# bluz_cr2477_v1.net
KiCad netlist of a schematic drawn in EAGLE
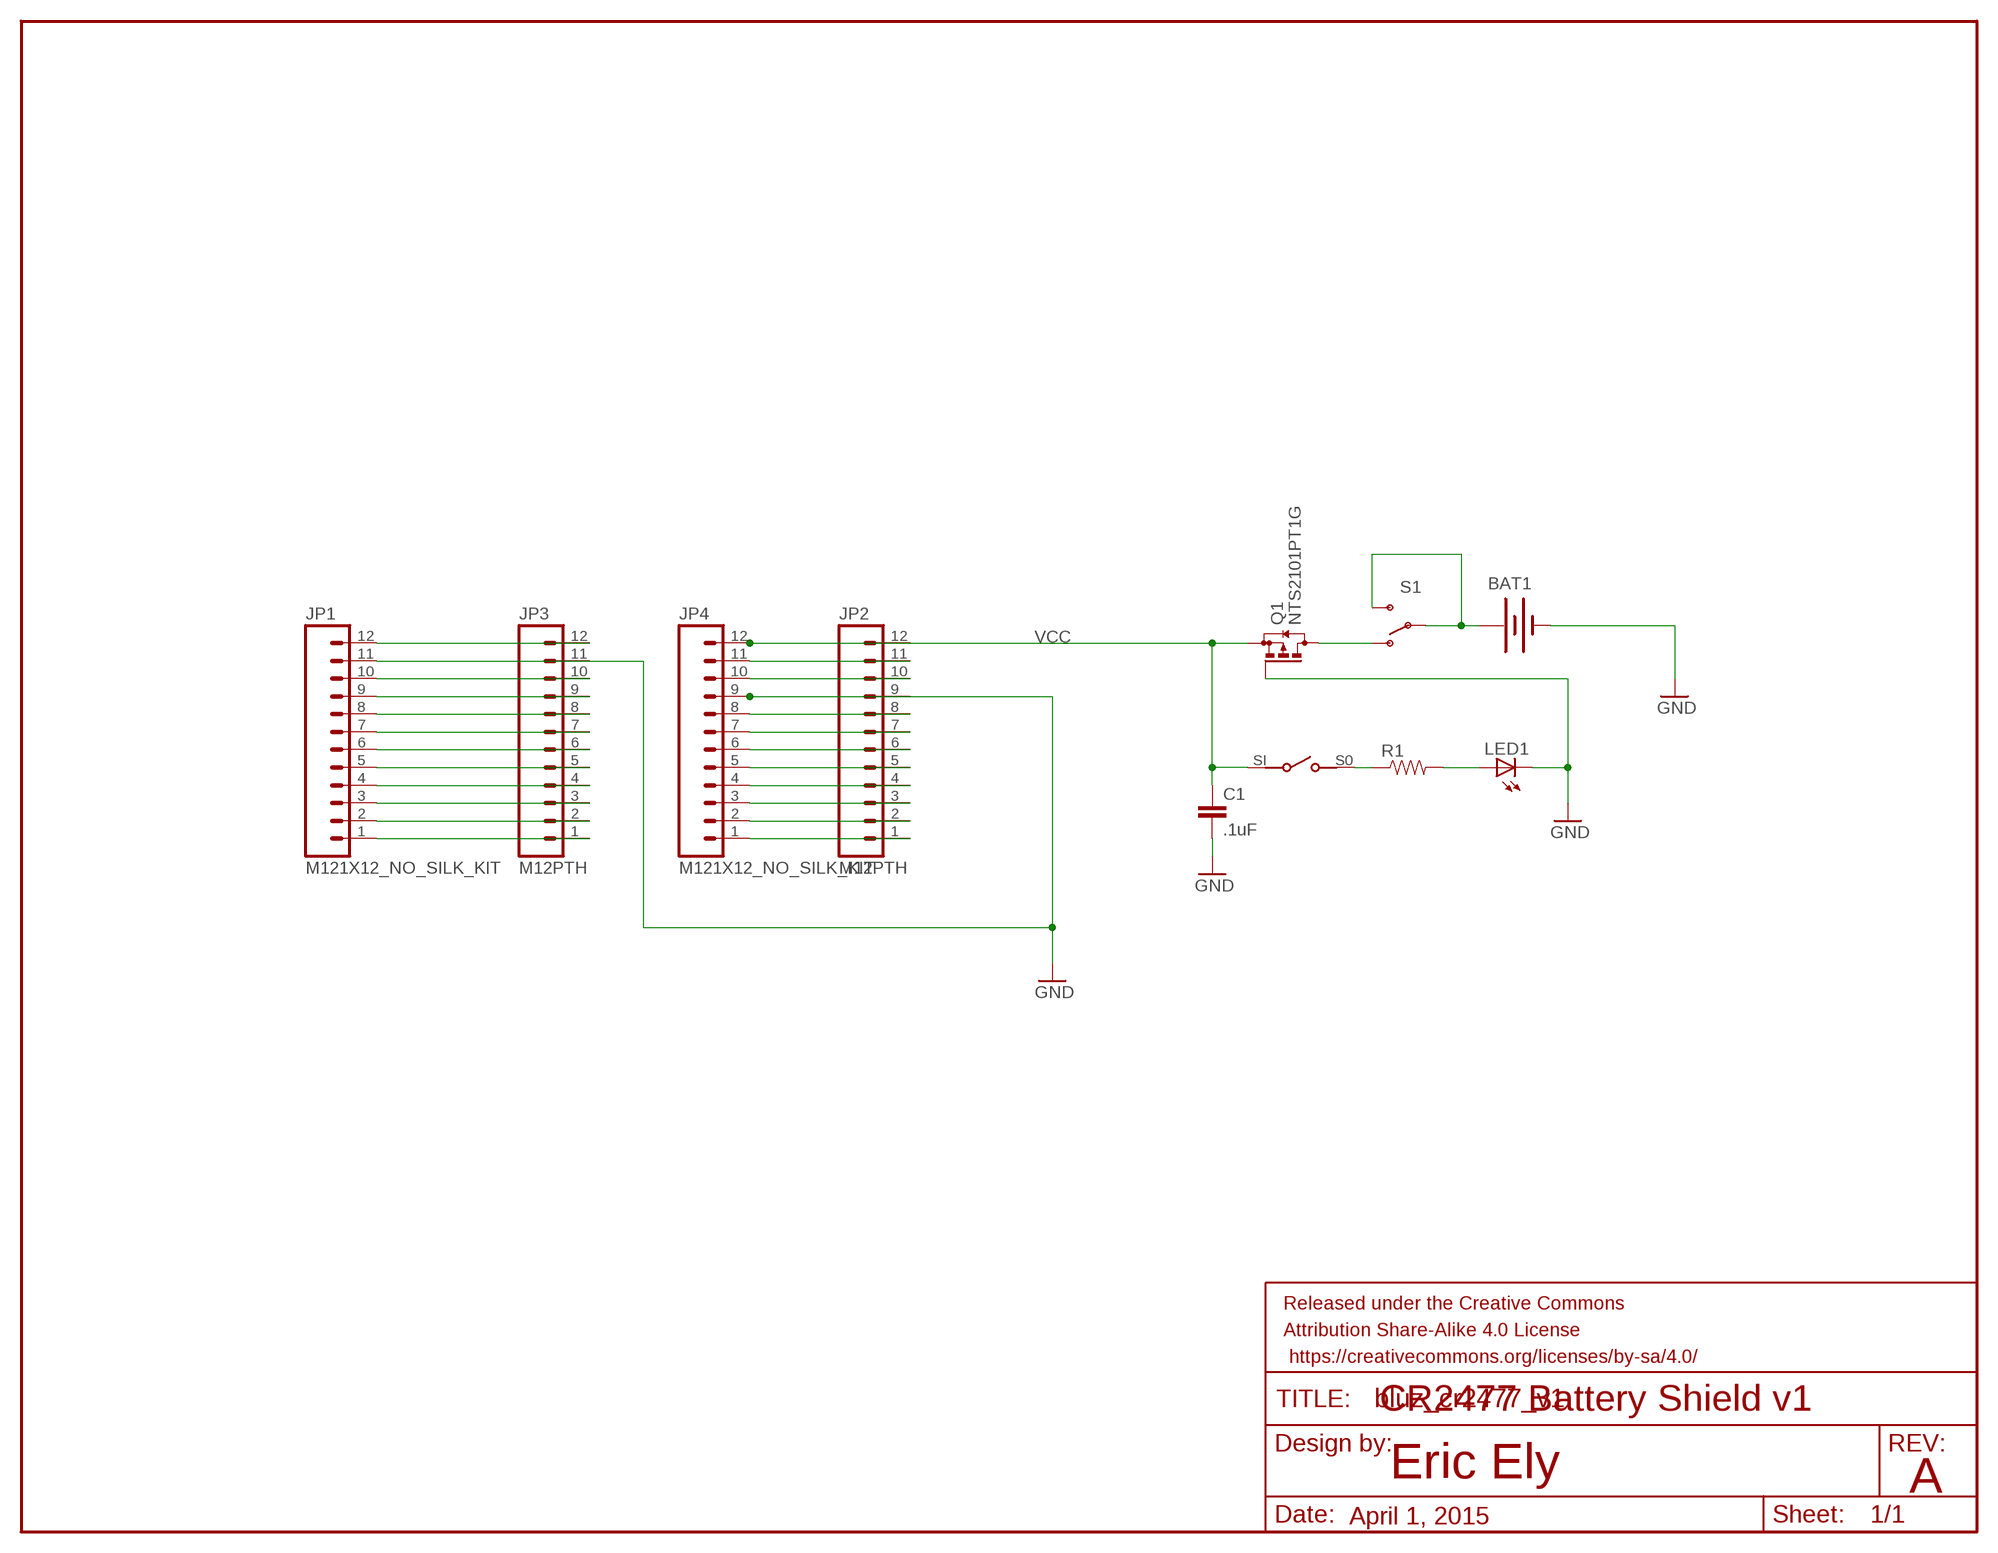
[diagram p0: schematic, sheet 1]

(export (version "E")
  (design (tool "Eeschema 10.0.6"))
  (components
    (comp (ref "BAT1")
      (value "BATTERY245PTH")
      (footprint "eagle-import:BATTCON_245MM_PTH")
      (libsource (lib "eagle-import") (part "BATTERY245PTH"))
    )
    (comp (ref "C1")
      (value ".1uF")
      (footprint "eagle-import:0603-CAP")
      (libsource (lib "eagle-import") (part "CAP0603-CAP"))
    )
    (comp (ref "FRAME1")
      (value "FRAME-LETTER")
      (footprint "eagle-import:CREATIVE_COMMONS")
      (libsource (lib "eagle-import") (part "FRAME-LETTER"))
    )
    (comp (ref "JP1")
      (value "M121X12_NO_SILK_KIT")
      (footprint "eagle-import:1X12_NO_SILK_KIT")
      (libsource (lib "eagle-import") (part "M121X12_NO_SILK_KIT"))
    )
    (comp (ref "JP2")
      (value "M12PTH")
      (footprint "eagle-import:1X12")
      (libsource (lib "eagle-import") (part "M12PTH"))
    )
    (comp (ref "JP3")
      (value "M12PTH")
      (footprint "eagle-import:1X12")
      (libsource (lib "eagle-import") (part "M12PTH"))
    )
    (comp (ref "JP4")
      (value "M121X12_NO_SILK_KIT")
      (footprint "eagle-import:1X12_NO_SILK_KIT")
      (libsource (lib "eagle-import") (part "M121X12_NO_SILK_KIT"))
    )
    (comp (ref "LED1")
      (value "LEDCHIPLED_0603")
      (footprint "eagle-import:CHIPLED_0603")
      (libsource (lib "eagle-import") (part "LEDCHIPLED_0603"))
    )
    (comp (ref "Q1")
      (value "NTS2101PT1G")
      (footprint "eagle-import:SOT323")
      (libsource (lib "eagle-import") (part "NTS2101PT1G"))
    )
    (comp (ref "R1")
      (value "RESISTOR0603-RES")
      (footprint "eagle-import:0603-RES")
      (libsource (lib "eagle-import") (part "RESISTOR0603-RES"))
    )
    (comp (ref "S1")
      (value "SWITCH-SPDTKIT")
      (footprint "eagle-import:SWITCH-SPDT_KIT")
      (libsource (lib "eagle-import") (part "SWITCH-SPDTKIT"))
    )
    (comp (ref "S2")
      (value "CHS-01TASMD")
      (footprint "eagle-import:CHS-01TA")
      (libsource (lib "eagle-import") (part "CHS-01TASMD"))
    )
  )
  (nets
    (net (code "1") (name "/VCC") (class "Default")
      (node (ref "C1") (pin "1") (pinfunction "1_1") (pintype "passive"))
      (node (ref "JP2") (pin "12") (pinfunction "12_12") (pintype "passive"))
      (node (ref "JP4") (pin "12") (pinfunction "12_12") (pintype "passive"))
      (node (ref "Q1") (pin "2") (pinfunction "S_2") (pintype "passive"))
      (node (ref "S2") (pin "SI") (pinfunction "S~{}_SI") (pintype "input"))
    )
    (net (code "2") (name "GND") (class "Default")
      (node (ref "BAT1") (pin "2") (pinfunction "-_2") (pintype "power_in"))
      (node (ref "C1") (pin "2") (pinfunction "2_2") (pintype "passive"))
      (node (ref "JP1") (pin "11") (pinfunction "11_11") (pintype "passive"))
      (node (ref "JP2") (pin "9") (pinfunction "9_9") (pintype "passive"))
      (node (ref "JP3") (pin "11") (pinfunction "11_11") (pintype "passive"))
      (node (ref "JP4") (pin "9") (pinfunction "9_9") (pintype "passive"))
      (node (ref "LED1") (pin "C") (pinfunction "C_C") (pintype "passive"))
      (node (ref "Q1") (pin "1") (pinfunction "G_1") (pintype "passive"))
    )
    (net (code "3") (name "Net-(BAT1-+)") (class "Default")
      (node (ref "BAT1") (pin "3") (pinfunction "+_3") (pintype "power_in"))
      (node (ref "S1") (pin "2") (pinfunction "P_2") (pintype "passive"))
      (node (ref "S1") (pin "3") (pinfunction "S_3") (pintype "passive"))
    )
    (net (code "4") (name "Net-(JP1-Pad1)") (class "Default")
      (node (ref "JP1") (pin "1") (pinfunction "1_1") (pintype "passive"))
      (node (ref "JP3") (pin "1") (pinfunction "1_1") (pintype "passive"))
    )
    (net (code "5") (name "Net-(JP1-Pad2)") (class "Default")
      (node (ref "JP1") (pin "2") (pinfunction "2_2") (pintype "passive"))
      (node (ref "JP3") (pin "2") (pinfunction "2_2") (pintype "passive"))
    )
    (net (code "6") (name "Net-(JP1-Pad3)") (class "Default")
      (node (ref "JP1") (pin "3") (pinfunction "3_3") (pintype "passive"))
      (node (ref "JP3") (pin "3") (pinfunction "3_3") (pintype "passive"))
    )
    (net (code "7") (name "Net-(JP1-Pad4)") (class "Default")
      (node (ref "JP1") (pin "4") (pinfunction "4_4") (pintype "passive"))
      (node (ref "JP3") (pin "4") (pinfunction "4_4") (pintype "passive"))
    )
    (net (code "8") (name "Net-(JP1-Pad5)") (class "Default")
      (node (ref "JP1") (pin "5") (pinfunction "5_5") (pintype "passive"))
      (node (ref "JP3") (pin "5") (pinfunction "5_5") (pintype "passive"))
    )
    (net (code "9") (name "Net-(JP1-Pad6)") (class "Default")
      (node (ref "JP1") (pin "6") (pinfunction "6_6") (pintype "passive"))
      (node (ref "JP3") (pin "6") (pinfunction "6_6") (pintype "passive"))
    )
    (net (code "10") (name "Net-(JP1-Pad7)") (class "Default")
      (node (ref "JP1") (pin "7") (pinfunction "7_7") (pintype "passive"))
      (node (ref "JP3") (pin "7") (pinfunction "7_7") (pintype "passive"))
    )
    (net (code "11") (name "Net-(JP1-Pad8)") (class "Default")
      (node (ref "JP1") (pin "8") (pinfunction "8_8") (pintype "passive"))
      (node (ref "JP3") (pin "8") (pinfunction "8_8") (pintype "passive"))
    )
    (net (code "12") (name "Net-(JP1-Pad9)") (class "Default")
      (node (ref "JP1") (pin "9") (pinfunction "9_9") (pintype "passive"))
      (node (ref "JP3") (pin "9") (pinfunction "9_9") (pintype "passive"))
    )
    (net (code "13") (name "Net-(JP1-Pad10)") (class "Default")
      (node (ref "JP1") (pin "10") (pinfunction "10_10") (pintype "passive"))
      (node (ref "JP3") (pin "10") (pinfunction "10_10") (pintype "passive"))
    )
    (net (code "14") (name "Net-(JP1-Pad12)") (class "Default")
      (node (ref "JP1") (pin "12") (pinfunction "12_12") (pintype "passive"))
      (node (ref "JP3") (pin "12") (pinfunction "12_12") (pintype "passive"))
    )
    (net (code "15") (name "Net-(JP2-Pad1)") (class "Default")
      (node (ref "JP2") (pin "1") (pinfunction "1_1") (pintype "passive"))
      (node (ref "JP4") (pin "1") (pinfunction "1_1") (pintype "passive"))
    )
    (net (code "16") (name "Net-(JP2-Pad2)") (class "Default")
      (node (ref "JP2") (pin "2") (pinfunction "2_2") (pintype "passive"))
      (node (ref "JP4") (pin "2") (pinfunction "2_2") (pintype "passive"))
    )
    (net (code "17") (name "Net-(JP2-Pad3)") (class "Default")
      (node (ref "JP2") (pin "3") (pinfunction "3_3") (pintype "passive"))
      (node (ref "JP4") (pin "3") (pinfunction "3_3") (pintype "passive"))
    )
    (net (code "18") (name "Net-(JP2-Pad4)") (class "Default")
      (node (ref "JP2") (pin "4") (pinfunction "4_4") (pintype "passive"))
      (node (ref "JP4") (pin "4") (pinfunction "4_4") (pintype "passive"))
    )
    (net (code "19") (name "Net-(JP2-Pad5)") (class "Default")
      (node (ref "JP2") (pin "5") (pinfunction "5_5") (pintype "passive"))
      (node (ref "JP4") (pin "5") (pinfunction "5_5") (pintype "passive"))
    )
    (net (code "20") (name "Net-(JP2-Pad6)") (class "Default")
      (node (ref "JP2") (pin "6") (pinfunction "6_6") (pintype "passive"))
      (node (ref "JP4") (pin "6") (pinfunction "6_6") (pintype "passive"))
    )
    (net (code "21") (name "Net-(JP2-Pad7)") (class "Default")
      (node (ref "JP2") (pin "7") (pinfunction "7_7") (pintype "passive"))
      (node (ref "JP4") (pin "7") (pinfunction "7_7") (pintype "passive"))
    )
    (net (code "22") (name "Net-(JP2-Pad8)") (class "Default")
      (node (ref "JP2") (pin "8") (pinfunction "8_8") (pintype "passive"))
      (node (ref "JP4") (pin "8") (pinfunction "8_8") (pintype "passive"))
    )
    (net (code "23") (name "Net-(JP2-Pad10)") (class "Default")
      (node (ref "JP2") (pin "10") (pinfunction "10_10") (pintype "passive"))
      (node (ref "JP4") (pin "10") (pinfunction "10_10") (pintype "passive"))
    )
    (net (code "24") (name "Net-(JP2-Pad11)") (class "Default")
      (node (ref "JP2") (pin "11") (pinfunction "11_11") (pintype "passive"))
      (node (ref "JP4") (pin "11") (pinfunction "11_11") (pintype "passive"))
    )
    (net (code "25") (name "Net-(LED1-PadA)") (class "Default")
      (node (ref "LED1") (pin "A") (pinfunction "A_A") (pintype "passive"))
      (node (ref "R1") (pin "2") (pinfunction "2_2") (pintype "passive"))
    )
    (net (code "26") (name "Net-(Q1-D)") (class "Default")
      (node (ref "Q1") (pin "3") (pinfunction "D_3") (pintype "passive"))
      (node (ref "S1") (pin "1") (pinfunction "O_1") (pintype "passive"))
    )
    (net (code "27") (name "Net-(S2-SO)") (class "Default")
      (node (ref "R1") (pin "1") (pinfunction "1_1") (pintype "passive"))
      (node (ref "S2") (pin "S0") (pinfunction "SO_S0") (pintype "output"))
    )
  )
)
